# 10125624A00.net
KiCad netlist of a schematic drawn in EAGLE
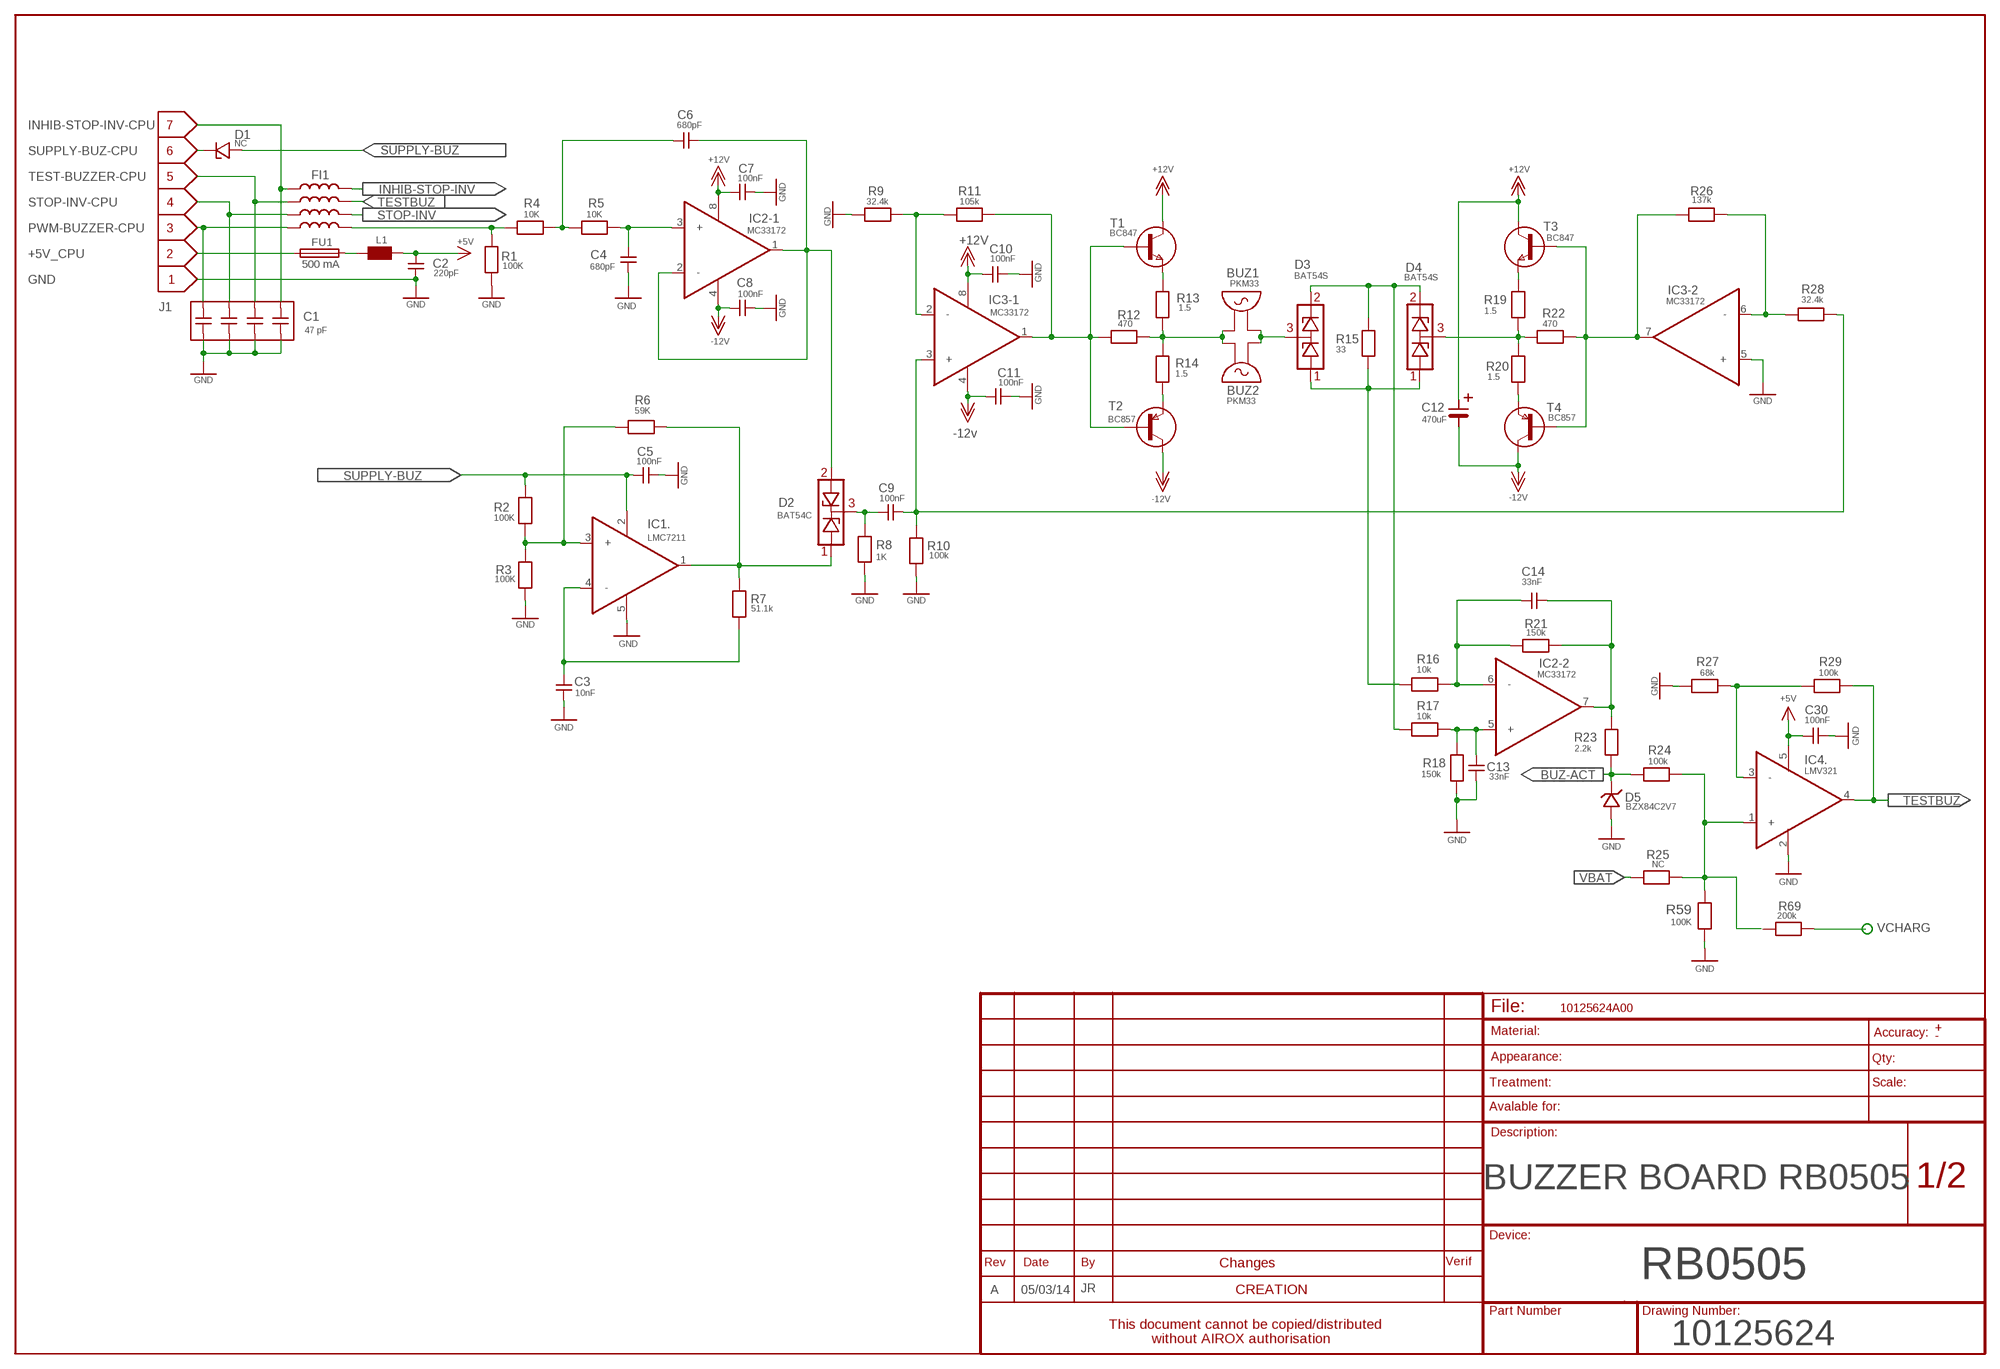
[diagram p0: schematic, sheet 1]
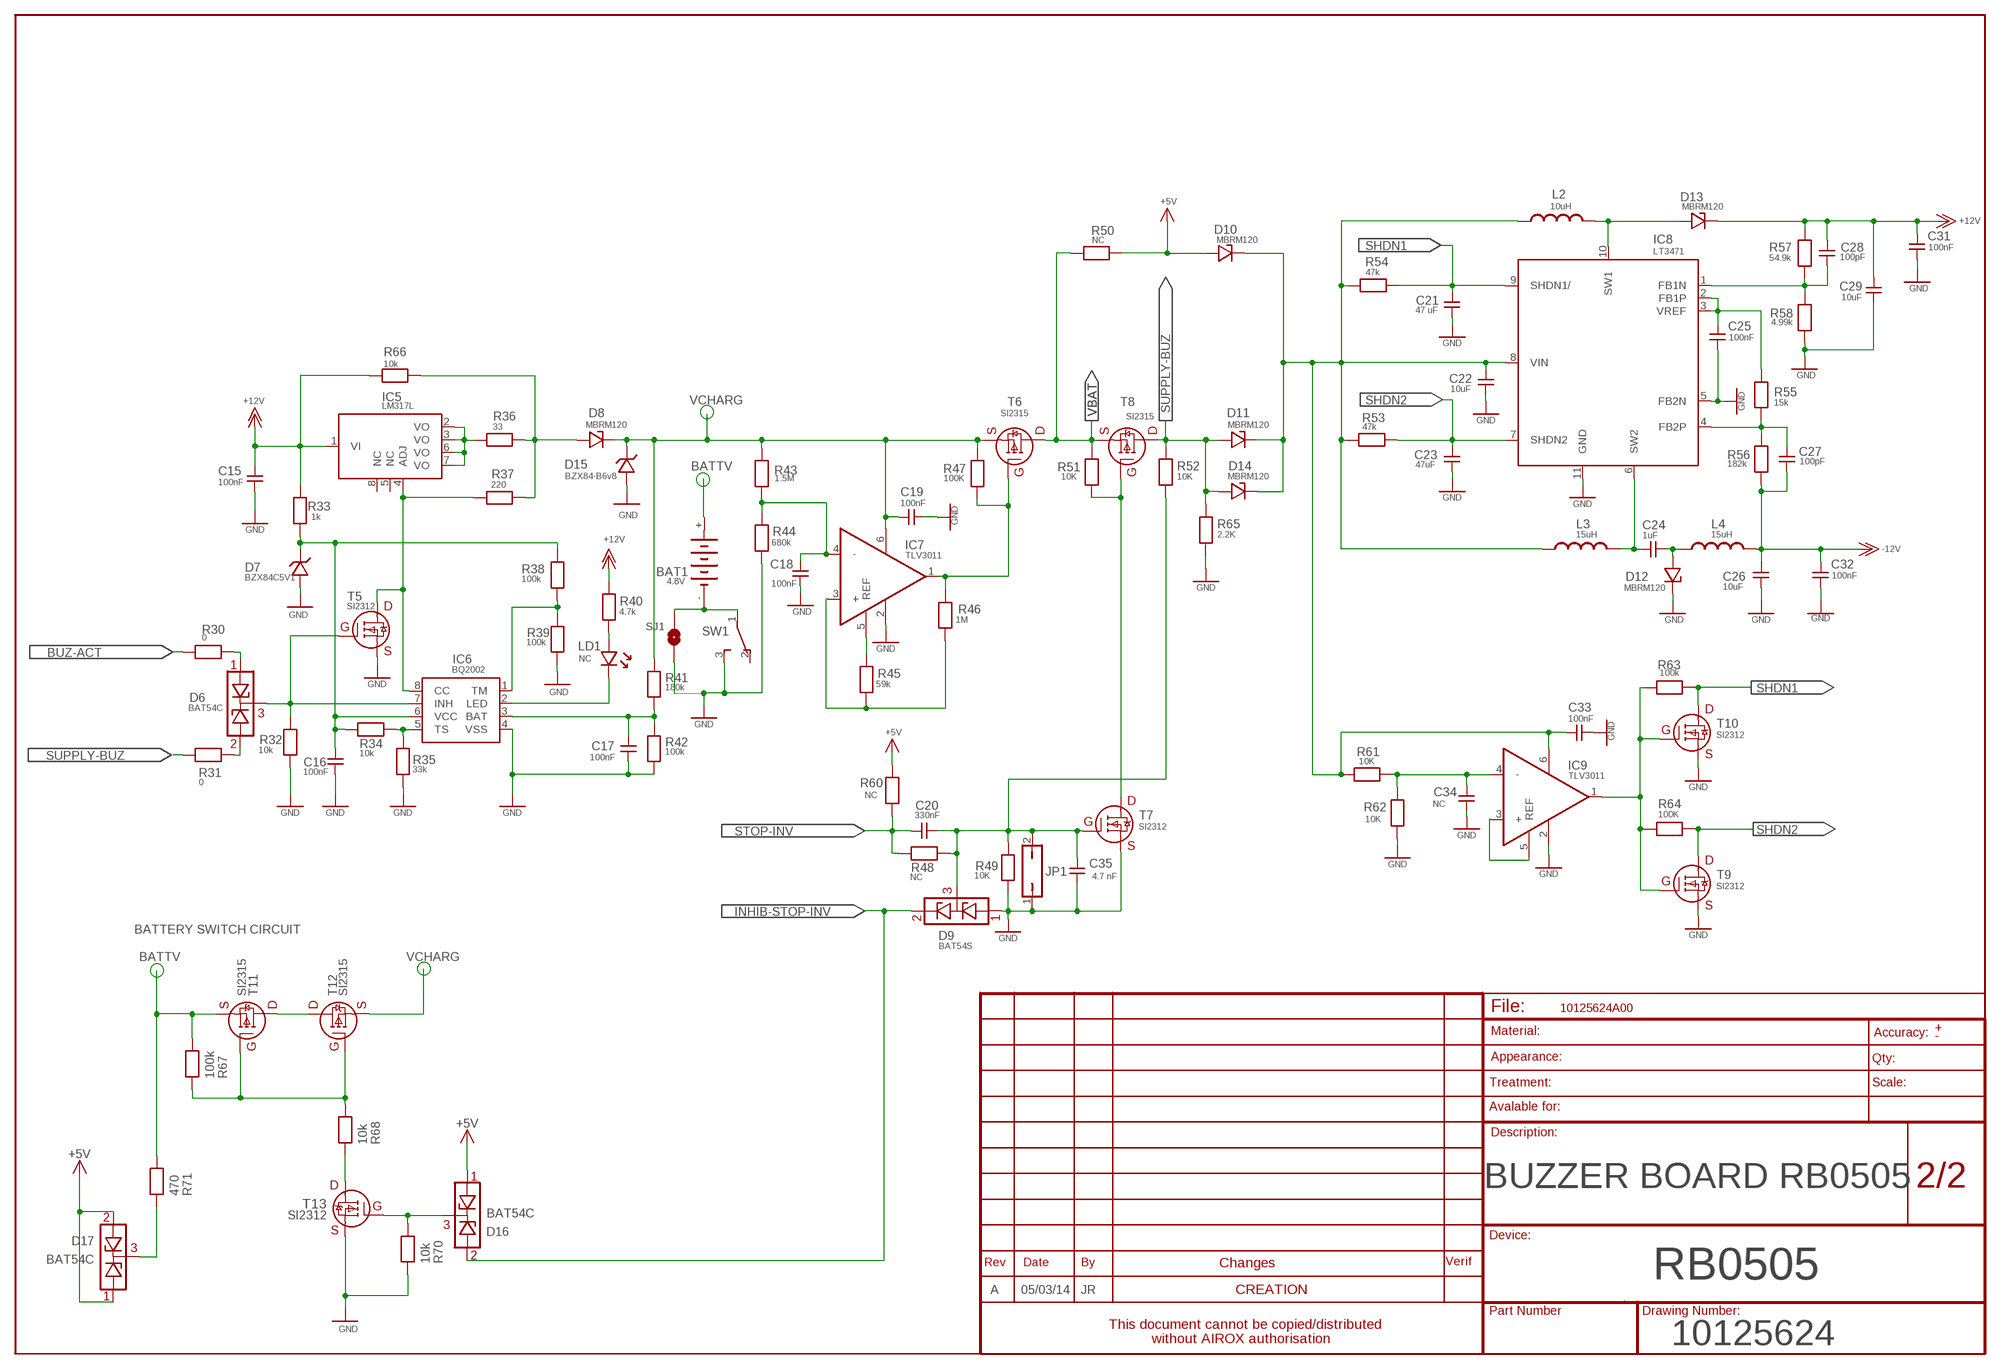
[diagram p1: schematic, sheet 2]

(export (version "E")
  (design (tool "Eeschema 10.0.6"))
  (components
    (comp (ref "BUZ1")
      (value "PKM33")
      (footprint "eagle-import:PKM33")
      (libsource (lib "eagle-import") (part "PKM33"))
    )
    (comp (ref "BUZ2")
      (value "PKM33")
      (footprint "eagle-import:PKM33")
      (libsource (lib "eagle-import") (part "PKM33"))
    )
    (comp (ref "C1")
      (value "47 pF")
      (footprint "eagle-import:RESEAU_1")
      (libsource (lib "eagle-import") (part "RESEAU_4C"))
    )
    (comp (ref "C2")
      (value "220pF")
      (footprint "eagle-import:C0805")
      (libsource (lib "eagle-import") (part "C0805"))
    )
    (comp (ref "C3")
      (value "10nF")
      (footprint "eagle-import:C0805")
      (libsource (lib "eagle-import") (part "C0805"))
    )
    (comp (ref "C4")
      (value "680pF")
      (footprint "eagle-import:C0603")
      (libsource (lib "eagle-import") (part "C0603"))
    )
    (comp (ref "C5")
      (value "100nF")
      (footprint "eagle-import:C0805")
      (libsource (lib "eagle-import") (part "C0805"))
    )
    (comp (ref "C6")
      (value "680pF")
      (footprint "eagle-import:C0603")
      (libsource (lib "eagle-import") (part "C0603"))
    )
    (comp (ref "C7")
      (value "100nF")
      (footprint "eagle-import:C0603")
      (libsource (lib "eagle-import") (part "C0603"))
    )
    (comp (ref "C8")
      (value "100nF")
      (footprint "eagle-import:C0603")
      (libsource (lib "eagle-import") (part "C0603"))
    )
    (comp (ref "C9")
      (value "100nF")
      (footprint "eagle-import:C0805")
      (libsource (lib "eagle-import") (part "CONDENSAT_CMS_C0805"))
    )
    (comp (ref "C10")
      (value "100nF")
      (footprint "eagle-import:C0603")
      (libsource (lib "eagle-import") (part "C0603"))
    )
    (comp (ref "C11")
      (value "100nF")
      (footprint "eagle-import:C0603")
      (libsource (lib "eagle-import") (part "C0603"))
    )
    (comp (ref "C12")
      (value "470uF")
      (footprint "eagle-import:MV100_F")
      (libsource (lib "eagle-import") (part "MV100?F50V"))
    )
    (comp (ref "C13")
      (value "33nF")
      (footprint "eagle-import:C0805")
      (libsource (lib "eagle-import") (part "CONDENSAT_CMS_C0805"))
    )
    (comp (ref "C14")
      (value "33nF")
      (footprint "eagle-import:C0805")
      (libsource (lib "eagle-import") (part "CONDENSAT_CMS_C0805"))
    )
    (comp (ref "C30")
      (value "100nF")
      (footprint "eagle-import:C0805")
      (libsource (lib "eagle-import") (part "CONDENSAT_CMS_C0805"))
    )
    (comp (ref "D1")
      (value "NC")
      (footprint "eagle-import:SOD87")
      (libsource (lib "eagle-import") (part "PRLL5819"))
    )
    (comp (ref "D2")
      (value "BAT54C")
      (footprint "eagle-import:SOT23_DI")
      (libsource (lib "eagle-import") (part "BAT54C"))
    )
    (comp (ref "D3")
      (value "BAT54S")
      (footprint "eagle-import:SOT23DIO")
      (libsource (lib "eagle-import") (part "BAT54S"))
    )
    (comp (ref "D4")
      (value "BAT54S")
      (footprint "eagle-import:SOT23DIO")
      (libsource (lib "eagle-import") (part "BAT54S"))
    )
    (comp (ref "D5")
      (value "BZX84C2V7")
      (footprint "eagle-import:SOT23DIO")
      (libsource (lib "eagle-import") (part "BZX84CXX"))
    )
    (comp (ref "FI1")
      (value "WE-FA")
      (footprint "eagle-import:WE-FA")
      (libsource (lib "eagle-import") (part "WE-FA"))
    )
    (comp (ref "FU1")
      (value "500 mA")
      (footprint "eagle-import:SLOBLO")
      (libsource (lib "eagle-import") (part "SLOBLO"))
    )
    (comp (ref "IC1")
      (value "LMC7211")
      (footprint "eagle-import:SOT23-5")
      (libsource (lib "eagle-import") (part "LMC7211"))
    )
    (comp (ref "IC2")
      (value "MC33172")
      (footprint "eagle-import:SO8")
      (libsource (lib "eagle-import") (part "OPA2604"))
    )
    (comp (ref "IC3")
      (value "MC33172")
      (footprint "eagle-import:SO8")
      (libsource (lib "eagle-import") (part "OPA2604"))
    )
    (comp (ref "IC4")
      (value "LMV321")
      (footprint "eagle-import:SOT23-5")
      (libsource (lib "eagle-import") (part "LMV321"))
    )
    (comp (ref "J1")
      (value "B7B_ZR_SM3_TF")
      (footprint "eagle-import:7B_ZR_SM3_TF")
      (libsource (lib "eagle-import") (part "B7B_ZR_SM3_TF"))
    )
    (comp (ref "L1")
      (value "742792")
      (footprint "eagle-import:0805")
      (libsource (lib "eagle-import") (part "742792"))
    )
    (comp (ref "R1")
      (value "100K")
      (footprint "eagle-import:R0805")
      (libsource (lib "eagle-import") (part "RESIST_CMS_R0805"))
    )
    (comp (ref "R2")
      (value "100K")
      (footprint "eagle-import:R0805")
      (libsource (lib "eagle-import") (part "R0805"))
    )
    (comp (ref "R3")
      (value "100K")
      (footprint "eagle-import:R0805")
      (libsource (lib "eagle-import") (part "R0805"))
    )
    (comp (ref "R4")
      (value "10K")
      (footprint "eagle-import:R0805")
      (libsource (lib "eagle-import") (part "RESIST_CMS_R0805"))
    )
    (comp (ref "R5")
      (value "10K")
      (footprint "eagle-import:R0805")
      (libsource (lib "eagle-import") (part "RESIST_CMS_R0805"))
    )
    (comp (ref "R6")
      (value "59K")
      (footprint "eagle-import:R0805")
      (libsource (lib "eagle-import") (part "R0805"))
    )
    (comp (ref "R7")
      (value "51.1k")
      (footprint "eagle-import:R0805")
      (libsource (lib "eagle-import") (part "R0805"))
    )
    (comp (ref "R8")
      (value "1K")
      (footprint "eagle-import:R0805")
      (libsource (lib "eagle-import") (part "R0805"))
    )
    (comp (ref "R9")
      (value "32.4k")
      (footprint "eagle-import:R0805")
      (libsource (lib "eagle-import") (part "RESIST_CMS_R0805"))
    )
    (comp (ref "R10")
      (value "100k")
      (footprint "eagle-import:R0805")
      (libsource (lib "eagle-import") (part "RESIST_CMS_R0805"))
    )
    (comp (ref "R11")
      (value "105k")
      (footprint "eagle-import:R0805")
      (libsource (lib "eagle-import") (part "RESIST_CMS_R0805"))
    )
    (comp (ref "R12")
      (value "470")
      (footprint "eagle-import:R0805")
      (libsource (lib "eagle-import") (part "RESIST_CMS_R0805"))
    )
    (comp (ref "R13")
      (value "1.5")
      (footprint "eagle-import:R0805")
      (libsource (lib "eagle-import") (part "RESIST_CMS_R0805"))
    )
    (comp (ref "R14")
      (value "1.5")
      (footprint "eagle-import:R0805")
      (libsource (lib "eagle-import") (part "RESIST_CMS_R0805"))
    )
    (comp (ref "R15")
      (value "33")
      (footprint "eagle-import:R0805")
      (libsource (lib "eagle-import") (part "RESIST_CMS_R0805"))
    )
    (comp (ref "R16")
      (value "10k")
      (footprint "eagle-import:R0805")
      (libsource (lib "eagle-import") (part "RESIST_CMS_R0805"))
    )
    (comp (ref "R17")
      (value "10k")
      (footprint "eagle-import:R0805")
      (libsource (lib "eagle-import") (part "RESIST_CMS_R0805"))
    )
    (comp (ref "R18")
      (value "150k")
      (footprint "eagle-import:R0805")
      (libsource (lib "eagle-import") (part "RESIST_CMS_R0805"))
    )
    (comp (ref "R19")
      (value "1.5")
      (footprint "eagle-import:R0805")
      (libsource (lib "eagle-import") (part "RESIST_CMS_R0805"))
    )
    (comp (ref "R20")
      (value "1.5")
      (footprint "eagle-import:R0805")
      (libsource (lib "eagle-import") (part "RESIST_CMS_R0805"))
    )
    (comp (ref "R21")
      (value "150k")
      (footprint "eagle-import:R0805")
      (libsource (lib "eagle-import") (part "RESIST_CMS_R0805"))
    )
    (comp (ref "R22")
      (value "470")
      (footprint "eagle-import:R0805")
      (libsource (lib "eagle-import") (part "RESIST_CMS_R0805"))
    )
    (comp (ref "R23")
      (value "2.2k")
      (footprint "eagle-import:R0805")
      (libsource (lib "eagle-import") (part "RESIST_CMS_R0805"))
    )
    (comp (ref "R24")
      (value "100k")
      (footprint "eagle-import:R0805")
      (libsource (lib "eagle-import") (part "RESIST_CMS_R0805"))
    )
    (comp (ref "R25")
      (value "NC")
      (footprint "eagle-import:R0805")
      (libsource (lib "eagle-import") (part "RESIST_CMS_R0805"))
    )
    (comp (ref "R26")
      (value "137k")
      (footprint "eagle-import:R0805")
      (libsource (lib "eagle-import") (part "RESIST_CMS_R0805"))
    )
    (comp (ref "R27")
      (value "68k")
      (footprint "eagle-import:R0805")
      (libsource (lib "eagle-import") (part "RESIST_CMS_R0805"))
    )
    (comp (ref "R28")
      (value "32.4k")
      (footprint "eagle-import:R0805")
      (libsource (lib "eagle-import") (part "RESIST_CMS_R0805"))
    )
    (comp (ref "R29")
      (value "100k")
      (footprint "eagle-import:R0805")
      (libsource (lib "eagle-import") (part "RESIST_CMS_R0805"))
    )
    (comp (ref "R59")
      (value "100K")
      (footprint "eagle-import:R0805")
      (libsource (lib "eagle-import") (part "RESIST_CMS_R0805"))
    )
    (comp (ref "R69")
      (value "200k")
      (footprint "eagle-import:R0805")
      (libsource (lib "eagle-import") (part "RESIST_CMS_R0805"))
    )
    (comp (ref "T1")
      (value "BC847")
      (footprint "eagle-import:SOT23")
      (libsource (lib "eagle-import") (part "BC847"))
    )
    (comp (ref "T2")
      (value "BC857")
      (footprint "eagle-import:SOT23")
      (libsource (lib "eagle-import") (part "BC547"))
    )
    (comp (ref "T3")
      (value "BC847")
      (footprint "eagle-import:SOT23")
      (libsource (lib "eagle-import") (part "BC847"))
    )
    (comp (ref "T4")
      (value "BC857")
      (footprint "eagle-import:SOT23")
      (libsource (lib "eagle-import") (part "BC547"))
    )
    (comp (ref "BAT1")
      (value "4.8V")
      (footprint "eagle-import:4V110R")
      (libsource (lib "eagle-import") (part "4V110R"))
    )
    (comp (ref "C15")
      (value "100nF")
      (footprint "eagle-import:C0805")
      (libsource (lib "eagle-import") (part "CONDENSA@4_C0805"))
    )
    (comp (ref "C16")
      (value "100nF")
      (footprint "eagle-import:C0805")
      (libsource (lib "eagle-import") (part "CONDENSAT_CMS_C0805"))
    )
    (comp (ref "C17")
      (value "100nF")
      (footprint "eagle-import:C0805")
      (libsource (lib "eagle-import") (part "CONDENSA@4_C0805"))
    )
    (comp (ref "C18")
      (value "100nF")
      (footprint "eagle-import:C0805")
      (libsource (lib "eagle-import") (part "CONDENSA@4_C0805"))
    )
    (comp (ref "C19")
      (value "100nF")
      (footprint "eagle-import:C0805")
      (libsource (lib "eagle-import") (part "CONDENSA@4_C0805"))
    )
    (comp (ref "C20")
      (value "330nF")
      (footprint "eagle-import:C0805")
      (libsource (lib "eagle-import") (part "CONDENSA@4_C0805"))
    )
    (comp (ref "C21")
      (value "47 uF")
      (footprint "eagle-import:C0805")
      (libsource (lib "eagle-import") (part "CONDENSAT_CMS_C0805"))
    )
    (comp (ref "C22")
      (value "10uF")
      (footprint "eagle-import:C0805")
      (libsource (lib "eagle-import") (part "CONDENSAT_CMS_C0805"))
    )
    (comp (ref "C23")
      (value "47uF")
      (footprint "eagle-import:C0805")
      (libsource (lib "eagle-import") (part "CONDENSAT_CMS_C0805"))
    )
    (comp (ref "C24")
      (value "1uF")
      (footprint "eagle-import:C0805")
      (libsource (lib "eagle-import") (part "CONDENSAT_CMS_C0805"))
    )
    (comp (ref "C25")
      (value "100nF")
      (footprint "eagle-import:C0805")
      (libsource (lib "eagle-import") (part "CONDENSAT_CMS_C0805"))
    )
    (comp (ref "C26")
      (value "10uF")
      (footprint "eagle-import:C0805")
      (libsource (lib "eagle-import") (part "CONDENSAT_CMS_C0805"))
    )
    (comp (ref "C27")
      (value "100pF")
      (footprint "eagle-import:C0805")
      (libsource (lib "eagle-import") (part "CONDENSAT_CMS_C0805"))
    )
    (comp (ref "C28")
      (value "100pF")
      (footprint "eagle-import:C0805")
      (libsource (lib "eagle-import") (part "CONDENSAT_CMS_C0805"))
    )
    (comp (ref "C29")
      (value "10uF")
      (footprint "eagle-import:C0805")
      (libsource (lib "eagle-import") (part "CONDENSAT_CMS_C0805"))
    )
    (comp (ref "C31")
      (value "100nF")
      (footprint "eagle-import:C0805")
      (libsource (lib "eagle-import") (part "CONDENSAT_CMS_C0805"))
    )
    (comp (ref "C32")
      (value "100nF")
      (footprint "eagle-import:C0805")
      (libsource (lib "eagle-import") (part "CONDENSAT_CMS_C0805"))
    )
    (comp (ref "C33")
      (value "100nF")
      (footprint "eagle-import:C0805")
      (libsource (lib "eagle-import") (part "CONDENSA@4_C0805"))
    )
    (comp (ref "C34")
      (value "NC")
      (footprint "eagle-import:C0805")
      (libsource (lib "eagle-import") (part "CONDENSA@4_C0805"))
    )
    (comp (ref "C35")
      (value "4.7 nF")
      (footprint "eagle-import:C0805")
      (libsource (lib "eagle-import") (part "CONDENSA@4_C0805"))
    )
    (comp (ref "D6")
      (value "BAT54C")
      (footprint "eagle-import:SOT23_DI")
      (libsource (lib "eagle-import") (part "BAT54C"))
    )
    (comp (ref "D7")
      (value "BZX84C5V1")
      (footprint "eagle-import:SOT23DIO")
      (libsource (lib "eagle-import") (part "BZX84CXX"))
    )
    (comp (ref "D8")
      (value "MBRM120")
      (footprint "eagle-import:SOD87")
      (libsource (lib "eagle-import") (part "PRLL5819"))
    )
    (comp (ref "D9")
      (value "BAT54S")
      (footprint "eagle-import:SOT23DIO")
      (libsource (lib "eagle-import") (part "BAT54S"))
    )
    (comp (ref "D10")
      (value "MBRM120")
      (footprint "eagle-import:SOD87")
      (libsource (lib "eagle-import") (part "PRLL5819"))
    )
    (comp (ref "D11")
      (value "MBRM120")
      (footprint "eagle-import:SOD87")
      (libsource (lib "eagle-import") (part "PRLL5819"))
    )
    (comp (ref "D12")
      (value "MBRM120")
      (footprint "eagle-import:SOD87")
      (libsource (lib "eagle-import") (part "PRLL5819"))
    )
    (comp (ref "D13")
      (value "MBRM120")
      (footprint "eagle-import:SOD87")
      (libsource (lib "eagle-import") (part "PRLL5819"))
    )
    (comp (ref "D14")
      (value "MBRM120")
      (footprint "eagle-import:SOD87")
      (libsource (lib "eagle-import") (part "PRLL5819"))
    )
    (comp (ref "D15")
      (value "BZX84-B6v8")
      (footprint "eagle-import:SOT23DIO")
      (libsource (lib "eagle-import") (part "BZX84CXX"))
    )
    (comp (ref "D16")
      (value "BAT54C")
      (footprint "eagle-import:SOT23_DI")
      (libsource (lib "eagle-import") (part "BAT54C"))
    )
    (comp (ref "D17")
      (value "BAT54C")
      (footprint "eagle-import:SOT23_DI")
      (libsource (lib "eagle-import") (part "BAT54C"))
    )
    (comp (ref "IC5")
      (value "LM317L")
      (footprint "eagle-import:SO8")
      (libsource (lib "eagle-import") (part "LM317L"))
    )
    (comp (ref "IC6")
      (value "BQ2002")
      (footprint "eagle-import:SO8")
      (libsource (lib "eagle-import") (part "BQ2002"))
    )
    (comp (ref "IC7")
      (value "TLV3011")
      (footprint "eagle-import:SOT23-6")
      (libsource (lib "eagle-import") (part "TLV3011"))
    )
    (comp (ref "IC8")
      (value "LT3471")
      (footprint "eagle-import:DFN10")
      (libsource (lib "eagle-import") (part "LT3471"))
    )
    (comp (ref "IC9")
      (value "TLV3011")
      (footprint "eagle-import:SOT23-6")
      (libsource (lib "eagle-import") (part "TLV3011"))
    )
    (comp (ref "JP1")
      (value "JP1Q")
      (footprint "eagle-import:JP1")
      (libsource (lib "eagle-import") (part "JP1Q"))
    )
    (comp (ref "L2")
      (value "10uH")
      (footprint "eagle-import:WE-TPC-MH")
      (libsource (lib "eagle-import") (part "WE-TPC-MH"))
    )
    (comp (ref "L3")
      (value "15uH")
      (footprint "eagle-import:WE-TPC-MH")
      (libsource (lib "eagle-import") (part "WE-TPC-MH"))
    )
    (comp (ref "L4")
      (value "15uH")
      (footprint "eagle-import:WE-TPC-MH")
      (libsource (lib "eagle-import") (part "WE-TPC-MH"))
    )
    (comp (ref "LD1")
      (value "NC")
      (footprint "eagle-import:LED3")
      (libsource (lib "eagle-import") (part "LED3"))
    )
    (comp (ref "R30")
      (value "0")
      (footprint "eagle-import:R0805")
      (libsource (lib "eagle-import") (part "R0805"))
    )
    (comp (ref "R31")
      (value "0")
      (footprint "eagle-import:R0805")
      (libsource (lib "eagle-import") (part "R0805"))
    )
    (comp (ref "R32")
      (value "10k")
      (footprint "eagle-import:R0805")
      (libsource (lib "eagle-import") (part "R0805"))
    )
    (comp (ref "R33")
      (value "1k")
      (footprint "eagle-import:R0805")
      (libsource (lib "eagle-import") (part "R0805"))
    )
    (comp (ref "R34")
      (value "10k")
      (footprint "eagle-import:R0805")
      (libsource (lib "eagle-import") (part "R0805"))
    )
    (comp (ref "R35")
      (value "33k")
      (footprint "eagle-import:R0805")
      (libsource (lib "eagle-import") (part "R0805"))
    )
    (comp (ref "R36")
      (value "33")
      (footprint "eagle-import:R0805")
      (libsource (lib "eagle-import") (part "R0805"))
    )
    (comp (ref "R37")
      (value "220")
      (footprint "eagle-import:R0805")
      (libsource (lib "eagle-import") (part "R0805"))
    )
    (comp (ref "R38")
      (value "100k")
      (footprint "eagle-import:R0805")
      (libsource (lib "eagle-import") (part "R0805"))
    )
    (comp (ref "R39")
      (value "100k")
      (footprint "eagle-import:R0805")
      (libsource (lib "eagle-import") (part "R0805"))
    )
    (comp (ref "R40")
      (value "4.7k")
      (footprint "eagle-import:R0805")
      (libsource (lib "eagle-import") (part "R0805"))
    )
    (comp (ref "R41")
      (value "180k")
      (footprint "eagle-import:R0805")
      (libsource (lib "eagle-import") (part "R0805"))
    )
    (comp (ref "R42")
      (value "100k")
      (footprint "eagle-import:R0805")
      (libsource (lib "eagle-import") (part "R0805"))
    )
    (comp (ref "R43")
      (value "1.5M")
      (footprint "eagle-import:R0805")
      (libsource (lib "eagle-import") (part "R0805"))
    )
    (comp (ref "R44")
      (value "680k")
      (footprint "eagle-import:R0805")
      (libsource (lib "eagle-import") (part "R0805"))
    )
    (comp (ref "R45")
      (value "59k")
      (footprint "eagle-import:R0805")
      (libsource (lib "eagle-import") (part "R0805"))
    )
    (comp (ref "R46")
      (value "1M")
      (footprint "eagle-import:R0805")
      (libsource (lib "eagle-import") (part "R0805"))
    )
    (comp (ref "R47")
      (value "100K")
      (footprint "eagle-import:R0805")
      (libsource (lib "eagle-import") (part "R0805"))
    )
    (comp (ref "R48")
      (value "NC")
      (footprint "eagle-import:R0805")
      (libsource (lib "eagle-import") (part "R0805"))
    )
    (comp (ref "R49")
      (value "10K")
      (footprint "eagle-import:R0805")
      (libsource (lib "eagle-import") (part "R0805"))
    )
    (comp (ref "R50")
      (value "NC")
      (footprint "eagle-import:R0805")
      (libsource (lib "eagle-import") (part "R0805"))
    )
    (comp (ref "R51")
      (value "10K")
      (footprint "eagle-import:R0805")
      (libsource (lib "eagle-import") (part "R0805"))
    )
    (comp (ref "R52")
      (value "10K")
      (footprint "eagle-import:R0805")
      (libsource (lib "eagle-import") (part "R0805"))
    )
    (comp (ref "R53")
      (value "47k")
      (footprint "eagle-import:R0805")
      (libsource (lib "eagle-import") (part "RESIST_CMS_R0805"))
    )
    (comp (ref "R54")
      (value "47k")
      (footprint "eagle-import:R0805")
      (libsource (lib "eagle-import") (part "RESIST_CMS_R0805"))
    )
    (comp (ref "R55")
      (value "15k")
      (footprint "eagle-import:R0805")
      (libsource (lib "eagle-import") (part "RESIST_CMS_R0805"))
    )
    (comp (ref "R56")
      (value "182k")
      (footprint "eagle-import:R0805")
      (libsource (lib "eagle-import") (part "RESIST_CMS_R0805"))
    )
    (comp (ref "R57")
      (value "54.9k")
      (footprint "eagle-import:R0805")
      (libsource (lib "eagle-import") (part "RESIST_CMS_R0805"))
    )
    (comp (ref "R58")
      (value "4.99k")
      (footprint "eagle-import:R0805")
      (libsource (lib "eagle-import") (part "RESIST_CMS_R0805"))
    )
    (comp (ref "R60")
      (value "NC")
      (footprint "eagle-import:R0805")
      (libsource (lib "eagle-import") (part "R0805"))
    )
    (comp (ref "R61")
      (value "10K")
      (footprint "eagle-import:R0805")
      (libsource (lib "eagle-import") (part "R0805"))
    )
    (comp (ref "R62")
      (value "10K")
      (footprint "eagle-import:R0805")
      (libsource (lib "eagle-import") (part "R0805"))
    )
    (comp (ref "R63")
      (value "100k")
      (footprint "eagle-import:R0805")
      (libsource (lib "eagle-import") (part "R0805"))
    )
    (comp (ref "R64")
      (value "100K")
      (footprint "eagle-import:R0805")
      (libsource (lib "eagle-import") (part "R0805"))
    )
    (comp (ref "R65")
      (value "2.2K")
      (footprint "eagle-import:R0805")
      (libsource (lib "eagle-import") (part "R0805"))
    )
    (comp (ref "R66")
      (value "10k")
      (footprint "eagle-import:R0805")
      (libsource (lib "eagle-import") (part "R0805"))
    )
    (comp (ref "R67")
      (value "100k")
      (footprint "eagle-import:R0805")
      (libsource (lib "eagle-import") (part "R0805"))
    )
    (comp (ref "R68")
      (value "10k")
      (footprint "eagle-import:R0805")
      (libsource (lib "eagle-import") (part "R0805"))
    )
    (comp (ref "R70")
      (value "10k")
      (footprint "eagle-import:R0805")
      (libsource (lib "eagle-import") (part "R0805"))
    )
    (comp (ref "R71")
      (value "470")
      (footprint "eagle-import:R0805")
      (libsource (lib "eagle-import") (part "R0805"))
    )
    (comp (ref "SJ1")
      (value "SJW")
      (footprint "eagle-import:SJW")
      (libsource (lib "eagle-import") (part "SJW"))
    )
    (comp (ref "SW1")
      (value "NK236")
      (footprint "eagle-import:NK236")
      (libsource (lib "eagle-import") (part "NK236"))
    )
    (comp (ref "T5")
      (value "SI2312")
      (footprint "eagle-import:SOT23MOS")
      (libsource (lib "eagle-import") (part "IRLML2803"))
    )
    (comp (ref "T6")
      (value "SI2315")
      (footprint "eagle-import:SOT23MOS")
      (libsource (lib "eagle-import") (part "IRLML5103"))
    )
    (comp (ref "T7")
      (value "SI2312")
      (footprint "eagle-import:SOT23MOS")
      (libsource (lib "eagle-import") (part "IRLML2803"))
    )
    (comp (ref "T8")
      (value "SI2315")
      (footprint "eagle-import:SOT23MOS")
      (libsource (lib "eagle-import") (part "IRLML5103"))
    )
    (comp (ref "T9")
      (value "SI2312")
      (footprint "eagle-import:SOT23MOS")
      (libsource (lib "eagle-import") (part "IRLML2803"))
    )
    (comp (ref "T10")
      (value "SI2312")
      (footprint "eagle-import:SOT23MOS")
      (libsource (lib "eagle-import") (part "IRLML2803"))
    )
    (comp (ref "T11")
      (value "SI2315")
      (footprint "eagle-import:SOT23MOS")
      (libsource (lib "eagle-import") (part "IRLML5103"))
    )
    (comp (ref "T12")
      (value "SI2315")
      (footprint "eagle-import:SOT23MOS")
      (libsource (lib "eagle-import") (part "IRLML5103"))
    )
    (comp (ref "T13")
      (value "SI2312")
      (footprint "eagle-import:SOT23MOS")
      (libsource (lib "eagle-import") (part "IRLML2803"))
    )
  )
  (nets
    (net (code "1") (name "+5V") (class "Default")
      (node (ref "C2") (pin "2") (pinfunction "2_2") (pintype "passive"))
      (node (ref "C30") (pin "1") (pinfunction "1_1") (pintype "passive"))
      (node (ref "D10") (pin "A") (pinfunction "A_A") (pintype "passive"))
      (node (ref "D16") (pin "1") (pinfunction "1_1") (pintype "passive"))
      (node (ref "D17") (pin "1") (pinfunction "1_1") (pintype "passive"))
      (node (ref "D17") (pin "2") (pinfunction "2_2") (pintype "bidirectional"))
      (node (ref "IC4") (pin "5") (pinfunction "VCC_5") (pintype "bidirectional"))
      (node (ref "L1") (pin "2") (pinfunction "P$2_2") (pintype "bidirectional"))
      (node (ref "R50") (pin "2") (pinfunction "2_2") (pintype "bidirectional"))
      (node (ref "R60") (pin "2") (pinfunction "2_2") (pintype "bidirectional"))
    )
    (net (code "2") (name "+5V_CPU") (class "Default")
      (node (ref "FU1") (pin "1") (pinfunction "1_1") (pintype "bidirectional"))
      (node (ref "J1") (pin "2") (pinfunction "2_2") (pintype "bidirectional"))
    )
    (net (code "3") (name "+12V") (class "Default")
      (node (ref "C10") (pin "2") (pinfunction "2_2") (pintype "passive"))
      (node (ref "C12") (pin "+") (pinfunction "+_+") (pintype "passive"))
      (node (ref "C15") (pin "2") (pinfunction "2_2") (pintype "passive"))
      (node (ref "C28") (pin "2") (pinfunction "2_2") (pintype "passive"))
      (node (ref "C29") (pin "2") (pinfunction "2_2") (pintype "passive"))
      (node (ref "C31") (pin "2") (pinfunction "2_2") (pintype "passive"))
      (node (ref "C7") (pin "1") (pinfunction "1_1") (pintype "passive"))
      (node (ref "D13") (pin "K") (pinfunction "K_K") (pintype "passive"))
      (node (ref "IC2") (pin "8") (pinfunction "VCC_8") (pintype "bidirectional"))
      (node (ref "IC3") (pin "8") (pinfunction "VCC_8") (pintype "bidirectional"))
      (node (ref "IC5") (pin "1") (pinfunction "VI_1") (pintype "bidirectional"))
      (node (ref "R33") (pin "2") (pinfunction "2_2") (pintype "bidirectional"))
      (node (ref "R40") (pin "1") (pinfunction "1_1") (pintype "bidirectional"))
      (node (ref "R57") (pin "1") (pinfunction "1_1") (pintype "bidirectional"))
      (node (ref "R66") (pin "2") (pinfunction "2_2") (pintype "bidirectional"))
      (node (ref "T1") (pin "C") (pinfunction "C_C") (pintype "passive"))
      (node (ref "T3") (pin "C") (pinfunction "C_C") (pintype "passive"))
    )
    (net (code "4") (name "-12V") (class "Default")
      (node (ref "C11") (pin "2") (pinfunction "2_2") (pintype "passive"))
      (node (ref "C12") (pin "-") (pinfunction "-_-") (pintype "passive"))
      (node (ref "C26") (pin "1") (pinfunction "1_1") (pintype "passive"))
      (node (ref "C27") (pin "1") (pinfunction "1_1") (pintype "passive"))
      (node (ref "C32") (pin "2") (pinfunction "2_2") (pintype "passive"))
      (node (ref "C8") (pin "1") (pinfunction "1_1") (pintype "passive"))
      (node (ref "IC2") (pin "4") (pinfunction "GND_4") (pintype "bidirectional"))
      (node (ref "IC3") (pin "4") (pinfunction "GND_4") (pintype "bidirectional"))
      (node (ref "L4") (pin "2") (pinfunction "2_2") (pintype "bidirectional"))
      (node (ref "R56") (pin "2") (pinfunction "2_2") (pintype "bidirectional"))
      (node (ref "T2") (pin "C") (pinfunction "C_C") (pintype "passive"))
      (node (ref "T4") (pin "C") (pinfunction "C_C") (pintype "passive"))
    )
    (net (code "5") (name "BATTV") (class "Default")
      (node (ref "R67") (pin "2") (pinfunction "2_2") (pintype "bidirectional"))
      (node (ref "R71") (pin "2") (pinfunction "2_2") (pintype "bidirectional"))
      (node (ref "T11") (pin "S") (pinfunction "S_S") (pintype "passive"))
    )
    (net (code "6") (name "BUZ-ACT") (class "Default")
      (node (ref "D5") (pin "3") (pinfunction "K_3") (pintype "passive"))
      (node (ref "R23") (pin "2") (pinfunction "2_2") (pintype "bidirectional"))
      (node (ref "R24") (pin "2") (pinfunction "2_2") (pintype "bidirectional"))
      (node (ref "R30") (pin "1") (pinfunction "1_1") (pintype "bidirectional"))
    )
    (net (code "7") (name "GND") (class "Default")
      (node (ref "C1") (pin "1") (pinfunction "1_1") (pintype "passive"))
      (node (ref "C1") (pin "2") (pinfunction "2_2") (pintype "passive"))
      (node (ref "C1") (pin "3") (pinfunction "3_3") (pintype "passive"))
      (node (ref "C1") (pin "4") (pinfunction "4_4") (pintype "passive"))
      (node (ref "C10") (pin "1") (pinfunction "1_1") (pintype "passive"))
      (node (ref "C11") (pin "1") (pinfunction "1_1") (pintype "passive"))
      (node (ref "C13") (pin "2") (pinfunction "2_2") (pintype "passive"))
      (node (ref "C15") (pin "1") (pinfunction "1_1") (pintype "passive"))
      (node (ref "C16") (pin "2") (pinfunction "2_2") (pintype "passive"))
      (node (ref "C17") (pin "1") (pinfunction "1_1") (pintype "passive"))
      (node (ref "C18") (pin "2") (pinfunction "2_2") (pintype "passive"))
      (node (ref "C19") (pin "2") (pinfunction "2_2") (pintype "passive"))
      (node (ref "C2") (pin "1") (pinfunction "1_1") (pintype "passive"))
      (node (ref "C21") (pin "1") (pinfunction "1_1") (pintype "passive"))
      (node (ref "C22") (pin "2") (pinfunction "2_2") (pintype "passive"))
      (node (ref "C23") (pin "1") (pinfunction "1_1") (pintype "passive"))
      (node (ref "C25") (pin "1") (pinfunction "1_1") (pintype "passive"))
      (node (ref "C26") (pin "2") (pinfunction "2_2") (pintype "passive"))
      (node (ref "C29") (pin "1") (pinfunction "1_1") (pintype "passive"))
      (node (ref "C3") (pin "1") (pinfunction "1_1") (pintype "passive"))
      (node (ref "C30") (pin "2") (pinfunction "2_2") (pintype "passive"))
      (node (ref "C31") (pin "1") (pinfunction "1_1") (pintype "passive"))
      (node (ref "C32") (pin "1") (pinfunction "1_1") (pintype "passive"))
      (node (ref "C33") (pin "2") (pinfunction "2_2") (pintype "passive"))
      (node (ref "C34") (pin "1") (pinfunction "1_1") (pintype "passive"))
      (node (ref "C35") (pin "1") (pinfunction "1_1") (pintype "passive"))
      (node (ref "C4") (pin "2") (pinfunction "2_2") (pintype "passive"))
      (node (ref "C5") (pin "2") (pinfunction "2_2") (pintype "passive"))
      (node (ref "C7") (pin "2") (pinfunction "2_2") (pintype "passive"))
      (node (ref "C8") (pin "2") (pinfunction "2_2") (pintype "passive"))
      (node (ref "D12") (pin "K") (pinfunction "K_K") (pintype "passive"))
      (node (ref "D15") (pin "1") (pinfunction "A_1") (pintype "passive"))
      (node (ref "D5") (pin "1") (pinfunction "A_1") (pintype "passive"))
      (node (ref "D7") (pin "1") (pinfunction "A_1") (pintype "passive"))
      (node (ref "D9") (pin "1") (pinfunction "1_1") (pintype "passive"))
      (node (ref "IC1") (pin "5") (pinfunction "GND_5") (pintype "bidirectional"))
      (node (ref "IC3") (pin "5") (pinfunction "+_5") (pintype "input"))
      (node (ref "IC4") (pin "2") (pinfunction "GND_2") (pintype "bidirectional"))
      (node (ref "IC6") (pin "4") (pinfunction "VSS_4") (pintype "bidirectional"))
      (node (ref "IC7") (pin "2") (pinfunction "VSS_2") (pintype "bidirectional"))
      (node (ref "IC8") (pin "11") (pinfunction "GND_11") (pintype "bidirectional"))
      (node (ref "IC8") (pin "5") (pinfunction "FB2N_5") (pintype "bidirectional"))
      (node (ref "IC9") (pin "2") (pinfunction "VSS_2") (pintype "bidirectional"))
      (node (ref "J1") (pin "1") (pinfunction "1_1") (pintype "bidirectional"))
      (node (ref "JP1") (pin "1") (pinfunction "1_1") (pintype "passive"))
      (node (ref "R1") (pin "1") (pinfunction "1_1") (pintype "bidirectional"))
      (node (ref "R10") (pin "1") (pinfunction "1_1") (pintype "bidirectional"))
      (node (ref "R18") (pin "1") (pinfunction "1_1") (pintype "bidirectional"))
      (node (ref "R27") (pin "2") (pinfunction "2_2") (pintype "bidirectional"))
      (node (ref "R3") (pin "1") (pinfunction "1_1") (pintype "bidirectional"))
      (node (ref "R32") (pin "1") (pinfunction "1_1") (pintype "bidirectional"))
      (node (ref "R35") (pin "1") (pinfunction "1_1") (pintype "bidirectional"))
      (node (ref "R39") (pin "1") (pinfunction "1_1") (pintype "bidirectional"))
      (node (ref "R42") (pin "2") (pinfunction "2_2") (pintype "bidirectional"))
      (node (ref "R44") (pin "1") (pinfunction "1_1") (pintype "bidirectional"))
      (node (ref "R49") (pin "1") (pinfunction "1_1") (pintype "bidirectional"))
      (node (ref "R58") (pin "2") (pinfunction "2_2") (pintype "bidirectional"))
      (node (ref "R59") (pin "1") (pinfunction "1_1") (pintype "bidirectional"))
      (node (ref "R62") (pin "1") (pinfunction "1_1") (pintype "bidirectional"))
      (node (ref "R65") (pin "1") (pinfunction "1_1") (pintype "bidirectional"))
      (node (ref "R70") (pin "1") (pinfunction "1_1") (pintype "bidirectional"))
      (node (ref "R8") (pin "2") (pinfunction "2_2") (pintype "bidirectional"))
      (node (ref "R9") (pin "1") (pinfunction "1_1") (pintype "bidirectional"))
      (node (ref "SJ1") (pin "1") (pinfunction "1_1") (pintype "passive"))
      (node (ref "SW1") (pin "3") (pinfunction "3_3") (pintype "passive"))
      (node (ref "T10") (pin "S") (pinfunction "S_S") (pintype "passive"))
      (node (ref "T13") (pin "S") (pinfunction "S_S") (pintype "passive"))
      (node (ref "T5") (pin "S") (pinfunction "S_S") (pintype "passive"))
      (node (ref "T7") (pin "S") (pinfunction "S_S") (pintype "passive"))
      (node (ref "T9") (pin "S") (pinfunction "S_S") (pintype "passive"))
    )
    (net (code "8") (name "INHIB-STOP-INV") (class "Default")
      (node (ref "D16") (pin "2") (pinfunction "2_2") (pintype "bidirectional"))
      (node (ref "D9") (pin "2") (pinfunction "2_2") (pintype "bidirectional"))
      (node (ref "FI1") (pin "L4A") (pinfunction "L4A_L4A") (pintype "bidirectional"))
    )
    (net (code "9") (name "INHIB-STOP-INV-CPU") (class "Default")
      (node (ref "C1") (pin "8") (pinfunction "8_8") (pintype "passive"))
      (node (ref "FI1") (pin "L4B") (pinfunction "L4B_L4B") (pintype "bidirectional"))
      (node (ref "J1") (pin "7") (pinfunction "7_7") (pintype "bidirectional"))
    )
    (net (code "10") (name "Net-(BAT1-Pad-)") (class "Default")
      (node (ref "BAT1") (pin "-") (pinfunction "-_-") (pintype "passive"))
      (node (ref "SJ1") (pin "2") (pinfunction "2_2") (pintype "passive"))
      (node (ref "SW1") (pin "1") (pinfunction "1_1") (pintype "passive"))
    )
    (net (code "11") (name "Net-(BUZ1-1)") (class "Default")
      (node (ref "BUZ1") (pin "IN+") (pinfunction "1_IN+") (pintype "passive"))
      (node (ref "BUZ2") (pin "IN+") (pinfunction "1_IN+") (pintype "passive"))
      (node (ref "D3") (pin "3") (pinfunction "3_3") (pintype "passive"))
    )
    (net (code "12") (name "Net-(BUZ1-2)") (class "Default")
      (node (ref "BUZ1") (pin "IN-") (pinfunction "2_IN-") (pintype "passive"))
      (node (ref "BUZ2") (pin "IN-") (pinfunction "2_IN-") (pintype "passive"))
      (node (ref "R12") (pin "2") (pinfunction "2_2") (pintype "bidirectional"))
      (node (ref "R13") (pin "1") (pinfunction "1_1") (pintype "bidirectional"))
      (node (ref "R14") (pin "2") (pinfunction "2_2") (pintype "bidirectional"))
    )
    (net (code "13") (name "Net-(C6-Pad2)") (class "Default")
      (node (ref "C6") (pin "2") (pinfunction "2_2") (pintype "passive"))
      (node (ref "R4") (pin "1") (pinfunction "1_1") (pintype "bidirectional"))
      (node (ref "R5") (pin "2") (pinfunction "2_2") (pintype "bidirectional"))
    )
    (net (code "14") (name "Net-(C9-Pad2)") (class "Default")
      (node (ref "C9") (pin "2") (pinfunction "2_2") (pintype "passive"))
      (node (ref "D2") (pin "3") (pinfunction "3_3") (pintype "passive"))
      (node (ref "R8") (pin "1") (pinfunction "1_1") (pintype "bidirectional"))
    )
    (net (code "15") (name "Net-(C20-Pad1)") (class "Default")
      (node (ref "C20") (pin "1") (pinfunction "1_1") (pintype "passive"))
      (node (ref "C35") (pin "2") (pinfunction "2_2") (pintype "passive"))
      (node (ref "D9") (pin "3") (pinfunction "3_3") (pintype "passive"))
      (node (ref "JP1") (pin "2") (pinfunction "2_2") (pintype "passive"))
      (node (ref "R48") (pin "2") (pinfunction "2_2") (pintype "bidirectional"))
      (node (ref "R49") (pin "2") (pinfunction "2_2") (pintype "bidirectional"))
      (node (ref "R52") (pin "1") (pinfunction "1_1") (pintype "bidirectional"))
      (node (ref "T7") (pin "G") (pinfunction "G_G") (pintype "passive"))
    )
    (net (code "16") (name "Net-(C24-Pad1)") (class "Default")
      (node (ref "C24") (pin "1") (pinfunction "1_1") (pintype "passive"))
      (node (ref "D12") (pin "A") (pinfunction "A_A") (pintype "passive"))
      (node (ref "L4") (pin "1") (pinfunction "1_1") (pintype "bidirectional"))
    )
    (net (code "17") (name "Net-(D3-Pad1)") (class "Default")
      (node (ref "D3") (pin "1") (pinfunction "1_1") (pintype "passive"))
      (node (ref "D4") (pin "1") (pinfunction "1_1") (pintype "passive"))
      (node (ref "R15") (pin "1") (pinfunction "1_1") (pintype "bidirectional"))
      (node (ref "R16") (pin "1") (pinfunction "1_1") (pintype "bidirectional"))
    )
    (net (code "18") (name "Net-(D3-Pad2)") (class "Default")
      (node (ref "D3") (pin "2") (pinfunction "2_2") (pintype "bidirectional"))
      (node (ref "D4") (pin "2") (pinfunction "2_2") (pintype "bidirectional"))
      (node (ref "R15") (pin "2") (pinfunction "2_2") (pintype "bidirectional"))
      (node (ref "R17") (pin "1") (pinfunction "1_1") (pintype "bidirectional"))
    )
    (net (code "19") (name "Net-(D4-Pad3)") (class "Default")
      (node (ref "D4") (pin "3") (pinfunction "3_3") (pintype "passive"))
      (node (ref "R19") (pin "1") (pinfunction "1_1") (pintype "bidirectional"))
      (node (ref "R20") (pin "2") (pinfunction "2_2") (pintype "bidirectional"))
      (node (ref "R22") (pin "1") (pinfunction "1_1") (pintype "bidirectional"))
    )
    (net (code "20") (name "Net-(D6-Pad1)") (class "Default")
      (node (ref "D6") (pin "1") (pinfunction "1_1") (pintype "passive"))
      (node (ref "R30") (pin "2") (pinfunction "2_2") (pintype "bidirectional"))
    )
    (net (code "21") (name "Net-(D6-Pad2)") (class "Default")
      (node (ref "D6") (pin "2") (pinfunction "2_2") (pintype "bidirectional"))
      (node (ref "R31") (pin "2") (pinfunction "2_2") (pintype "bidirectional"))
    )
    (net (code "22") (name "Net-(D7-K)") (class "Default")
      (node (ref "C16") (pin "1") (pinfunction "1_1") (pintype "passive"))
      (node (ref "D7") (pin "3") (pinfunction "K_3") (pintype "passive"))
      (node (ref "IC6") (pin "6") (pinfunction "VCC_6") (pintype "bidirectional"))
      (node (ref "R33") (pin "1") (pinfunction "1_1") (pintype "bidirectional"))
      (node (ref "R34") (pin "2") (pinfunction "2_2") (pintype "bidirectional"))
      (node (ref "R38") (pin "2") (pinfunction "2_2") (pintype "bidirectional"))
    )
    (net (code "23") (name "Net-(D8-PadA)") (class "Default")
      (node (ref "D8") (pin "A") (pinfunction "A_A") (pintype "passive"))
      (node (ref "R36") (pin "1") (pinfunction "1_1") (pintype "bidirectional"))
      (node (ref "R37") (pin "1") (pinfunction "1_1") (pintype "bidirectional"))
      (node (ref "R66") (pin "1") (pinfunction "1_1") (pintype "bidirectional"))
    )
    (net (code "24") (name "Net-(D16-Pad3)") (class "Default")
      (node (ref "D16") (pin "3") (pinfunction "3_3") (pintype "passive"))
      (node (ref "R70") (pin "2") (pinfunction "2_2") (pintype "bidirectional"))
      (node (ref "T13") (pin "G") (pinfunction "G_G") (pintype "passive"))
    )
    (net (code "25") (name "Net-(D17-Pad3)") (class "Default")
      (node (ref "D17") (pin "3") (pinfunction "3_3") (pintype "passive"))
      (node (ref "R71") (pin "1") (pinfunction "1_1") (pintype "bidirectional"))
    )
    (net (code "26") (name "Net-(FI1-PadL1A)") (class "Default")
      (node (ref "FI1") (pin "L1A") (pinfunction "L1A_L1A") (pintype "bidirectional"))
      (node (ref "R1") (pin "2") (pinfunction "2_2") (pintype "bidirectional"))
      (node (ref "R4") (pin "2") (pinfunction "2_2") (pintype "bidirectional"))
    )
    (net (code "27") (name "Net-(IC1A-+)") (class "Default")
      (node (ref "IC1") (pin "3") (pinfunction "+_3") (pintype "input"))
      (node (ref "R2") (pin "1") (pinfunction "1_1") (pintype "bidirectional"))
      (node (ref "R3") (pin "2") (pinfunction "2_2") (pintype "bidirectional"))
      (node (ref "R6") (pin "1") (pinfunction "1_1") (pintype "bidirectional"))
    )
    (net (code "28") (name "Net-(IC1A--)") (class "Default")
      (node (ref "C3") (pin "2") (pinfunction "2_2") (pintype "passive"))
      (node (ref "IC1") (pin "4") (pinfunction "-_4") (pintype "input"))
      (node (ref "R7") (pin "1") (pinfunction "1_1") (pintype "bidirectional"))
    )
    (net (code "29") (name "Net-(IC1A-OUT)") (class "Default")
      (node (ref "D2") (pin "1") (pinfunction "1_1") (pintype "passive"))
      (node (ref "IC1") (pin "1") (pinfunction "OUT_1") (pintype "output"))
      (node (ref "R6") (pin "2") (pinfunction "2_2") (pintype "bidirectional"))
      (node (ref "R7") (pin "2") (pinfunction "2_2") (pintype "bidirectional"))
    )
    (net (code "30") (name "Net-(IC2A-+)") (class "Default")
      (node (ref "C4") (pin "1") (pinfunction "1_1") (pintype "passive"))
      (node (ref "IC2") (pin "3") (pinfunction "+_3") (pintype "input"))
      (node (ref "R5") (pin "1") (pinfunction "1_1") (pintype "bidirectional"))
    )
    (net (code "31") (name "Net-(IC2A--)") (class "Default")
      (node (ref "C6") (pin "1") (pinfunction "1_1") (pintype "passive"))
      (node (ref "D2") (pin "2") (pinfunction "2_2") (pintype "bidirectional"))
      (node (ref "IC2") (pin "1") (pinfunction "OUT_1") (pintype "output"))
      (node (ref "IC2") (pin "2") (pinfunction "-_2") (pintype "input"))
    )
    (net (code "32") (name "Net-(IC2B-+)") (class "Default")
      (node (ref "C13") (pin "1") (pinfunction "1_1") (pintype "passive"))
      (node (ref "IC2") (pin "5") (pinfunction "+_5") (pintype "input"))
      (node (ref "R17") (pin "2") (pinfunction "2_2") (pintype "bidirectional"))
      (node (ref "R18") (pin "2") (pinfunction "2_2") (pintype "bidirectional"))
    )
    (net (code "33") (name "Net-(IC2B--)") (class "Default")
      (node (ref "C14") (pin "1") (pinfunction "1_1") (pintype "passive"))
      (node (ref "IC2") (pin "6") (pinfunction "-_6") (pintype "input"))
      (node (ref "R16") (pin "2") (pinfunction "2_2") (pintype "bidirectional"))
      (node (ref "R21") (pin "1") (pinfunction "1_1") (pintype "bidirectional"))
    )
    (net (code "34") (name "Net-(IC2B-OUT)") (class "Default")
      (node (ref "C14") (pin "2") (pinfunction "2_2") (pintype "passive"))
      (node (ref "IC2") (pin "7") (pinfunction "OUT_7") (pintype "output"))
      (node (ref "R21") (pin "2") (pinfunction "2_2") (pintype "bidirectional"))
      (node (ref "R23") (pin "1") (pinfunction "1_1") (pintype "bidirectional"))
    )
    (net (code "35") (name "Net-(IC3A-+)") (class "Default")
      (node (ref "C9") (pin "1") (pinfunction "1_1") (pintype "passive"))
      (node (ref "IC3") (pin "3") (pinfunction "+_3") (pintype "input"))
      (node (ref "R10") (pin "2") (pinfunction "2_2") (pintype "bidirectional"))
      (node (ref "R28") (pin "2") (pinfunction "2_2") (pintype "bidirectional"))
    )
    (net (code "36") (name "Net-(IC3A--)") (class "Default")
      (node (ref "IC3") (pin "2") (pinfunction "-_2") (pintype "input"))
      (node (ref "R11") (pin "1") (pinfunction "1_1") (pintype "bidirectional"))
      (node (ref "R9") (pin "2") (pinfunction "2_2") (pintype "bidirectional"))
    )
    (net (code "37") (name "Net-(IC3A-OUT)") (class "Default")
      (node (ref "IC3") (pin "1") (pinfunction "OUT_1") (pintype "output"))
      (node (ref "R11") (pin "2") (pinfunction "2_2") (pintype "bidirectional"))
      (node (ref "R12") (pin "1") (pinfunction "1_1") (pintype "bidirectional"))
      (node (ref "T1") (pin "B") (pinfunction "B_B") (pintype "passive"))
      (node (ref "T2") (pin "B") (pinfunction "B_B") (pintype "passive"))
    )
    (net (code "38") (name "Net-(IC3B--)") (class "Default")
      (node (ref "IC3") (pin "6") (pinfunction "-_6") (pintype "input"))
      (node (ref "R26") (pin "2") (pinfunction "2_2") (pintype "bidirectional"))
      (node (ref "R28") (pin "1") (pinfunction "1_1") (pintype "bidirectional"))
    )
    (net (code "39") (name "Net-(IC3B-OUT)") (class "Default")
      (node (ref "IC3") (pin "7") (pinfunction "OUT_7") (pintype "output"))
      (node (ref "R22") (pin "2") (pinfunction "2_2") (pintype "bidirectional"))
      (node (ref "R26") (pin "1") (pinfunction "1_1") (pintype "bidirectional"))
      (node (ref "T3") (pin "B") (pinfunction "B_B") (pintype "passive"))
      (node (ref "T4") (pin "B") (pinfunction "B_B") (pintype "passive"))
    )
    (net (code "40") (name "Net-(IC4A-+)") (class "Default")
      (node (ref "IC4") (pin "1") (pinfunction "+_1") (pintype "input"))
      (node (ref "R24") (pin "1") (pinfunction "1_1") (pintype "bidirectional"))
      (node (ref "R25") (pin "1") (pinfunction "1_1") (pintype "bidirectional"))
      (node (ref "R59") (pin "2") (pinfunction "2_2") (pintype "bidirectional"))
    )
    (net (code "41") (name "Net-(IC4A--)") (class "Default")
      (node (ref "IC4") (pin "3") (pinfunction "-_3") (pintype "input"))
      (node (ref "R27") (pin "1") (pinfunction "1_1") (pintype "bidirectional"))
      (node (ref "R29") (pin "2") (pinfunction "2_2") (pintype "bidirectional"))
    )
    (net (code "42") (name "Net-(IC5-ADJ)") (class "Default")
      (node (ref "IC5") (pin "4") (pinfunction "ADJ_4") (pintype "bidirectional"))
      (node (ref "IC6") (pin "8") (pinfunction "CC_8") (pintype "bidirectional"))
      (node (ref "R37") (pin "2") (pinfunction "2_2") (pintype "bidirectional"))
      (node (ref "T5") (pin "D") (pinfunction "D_D") (pintype "passive"))
    )
    (net (code "43") (name "Net-(IC5-VO-Pad2)") (class "Default")
      (node (ref "IC5") (pin "2") (pinfunction "VO_2") (pintype "bidirectional"))
      (node (ref "IC5") (pin "3") (pinfunction "VO_3") (pintype "bidirectional"))
      (node (ref "IC5") (pin "6") (pinfunction "VO_6") (pintype "bidirectional"))
      (node (ref "IC5") (pin "7") (pinfunction "VO_7") (pintype "bidirectional"))
      (node (ref "R36") (pin "2") (pinfunction "2_2") (pintype "bidirectional"))
    )
    (net (code "44") (name "Net-(IC6-BAT)") (class "Default")
      (node (ref "C17") (pin "2") (pinfunction "2_2") (pintype "passive"))
      (node (ref "IC6") (pin "3") (pinfunction "BAT_3") (pintype "bidirectional"))
      (node (ref "R41") (pin "2") (pinfunction "2_2") (pintype "bidirectional"))
      (node (ref "R42") (pin "1") (pinfunction "1_1") (pintype "bidirectional"))
    )
    (net (code "45") (name "Net-(IC6-INH)") (class "Default")
      (node (ref "D6") (pin "3") (pinfunction "3_3") (pintype "passive"))
      (node (ref "IC6") (pin "7") (pinfunction "INH_7") (pintype "bidirectional"))
      (node (ref "R32") (pin "2") (pinfunction "2_2") (pintype "bidirectional"))
      (node (ref "T5") (pin "G") (pinfunction "G_G") (pintype "passive"))
    )
    (net (code "46") (name "Net-(IC6-LED)") (class "Default")
      (node (ref "IC6") (pin "2") (pinfunction "LED_2") (pintype "bidirectional"))
      (node (ref "LD1") (pin "K") (pinfunction "K_K") (pintype "passive"))
    )
    (net (code "47") (name "Net-(IC6-TM)") (class "Default")
      (node (ref "IC6") (pin "1") (pinfunction "TM_1") (pintype "bidirectional"))
      (node (ref "R38") (pin "1") (pinfunction "1_1") (pintype "bidirectional"))
      (node (ref "R39") (pin "2") (pinfunction "2_2") (pintype "bidirectional"))
    )
    (net (code "48") (name "Net-(IC6-TS)") (class "Default")
      (node (ref "IC6") (pin "5") (pinfunction "TS_5") (pintype "bidirectional"))
      (node (ref "R34") (pin "1") (pinfunction "1_1") (pintype "bidirectional"))
      (node (ref "R35") (pin "2") (pinfunction "2_2") (pintype "bidirectional"))
    )
    (net (code "49") (name "Net-(IC7-+)") (class "Default")
      (node (ref "IC7") (pin "3") (pinfunction "+_3") (pintype "input"))
      (node (ref "R45") (pin "1") (pinfunction "1_1") (pintype "bidirectional"))
      (node (ref "R46") (pin "1") (pinfunction "1_1") (pintype "bidirectional"))
    )
    (net (code "50") (name "Net-(IC7--)") (class "Default")
      (node (ref "C18") (pin "1") (pinfunction "1_1") (pintype "passive"))
      (node (ref "IC7") (pin "4") (pinfunction "-_4") (pintype "input"))
      (node (ref "R43") (pin "1") (pinfunction "1_1") (pintype "bidirectional"))
      (node (ref "R44") (pin "2") (pinfunction "2_2") (pintype "bidirectional"))
    )
    (net (code "51") (name "Net-(IC7-OUT)") (class "Default")
      (node (ref "IC7") (pin "1") (pinfunction "OUT_1") (pintype "output"))
      (node (ref "R46") (pin "2") (pinfunction "2_2") (pintype "bidirectional"))
      (node (ref "R47") (pin "1") (pinfunction "1_1") (pintype "bidirectional"))
      (node (ref "T6") (pin "G") (pinfunction "G_G") (pintype "passive"))
    )
    (net (code "52") (name "Net-(IC7-REF)") (class "Default")
      (node (ref "IC7") (pin "5") (pinfunction "REF_5") (pintype "bidirectional"))
      (node (ref "R45") (pin "2") (pinfunction "2_2") (pintype "bidirectional"))
    )
    (net (code "53") (name "Net-(IC8-FB1N)") (class "Default")
      (node (ref "C28") (pin "1") (pinfunction "1_1") (pintype "passive"))
      (node (ref "IC8") (pin "1") (pinfunction "FB1N_1") (pintype "bidirectional"))
      (node (ref "R57") (pin "2") (pinfunction "2_2") (pintype "bidirectional"))
      (node (ref "R58") (pin "1") (pinfunction "1_1") (pintype "bidirectional"))
    )
    (net (code "54") (name "Net-(IC8-FB1P)") (class "Default")
      (node (ref "C25") (pin "2") (pinfunction "2_2") (pintype "passive"))
      (node (ref "IC8") (pin "2") (pinfunction "FB1P_2") (pintype "bidirectional"))
      (node (ref "IC8") (pin "3") (pinfunction "VREF_3") (pintype "bidirectional"))
      (node (ref "R55") (pin "1") (pinfunction "1_1") (pintype "bidirectional"))
    )
    (net (code "55") (name "Net-(IC8-FB2P)") (class "Default")
      (node (ref "C27") (pin "2") (pinfunction "2_2") (pintype "passive"))
      (node (ref "IC8") (pin "4") (pinfunction "FB2P_4") (pintype "bidirectional"))
      (node (ref "R55") (pin "2") (pinfunction "2_2") (pintype "bidirectional"))
      (node (ref "R56") (pin "1") (pinfunction "1_1") (pintype "bidirectional"))
    )
    (net (code "56") (name "Net-(IC8-SW1)") (class "Default")
      (node (ref "D13") (pin "A") (pinfunction "A_A") (pintype "passive"))
      (node (ref "IC8") (pin "10") (pinfunction "SW1_10") (pintype "bidirectional"))
      (node (ref "L2") (pin "2") (pinfunction "2_2") (pintype "bidirectional"))
    )
    (net (code "57") (name "Net-(IC8-SW2)") (class "Default")
      (node (ref "C24") (pin "2") (pinfunction "2_2") (pintype "passive"))
      (node (ref "IC8") (pin "6") (pinfunction "SW2_6") (pintype "bidirectional"))
      (node (ref "L3") (pin "2") (pinfunction "2_2") (pintype "bidirectional"))
    )
    (net (code "58") (name "Net-(IC8-VIN)") (class "Default")
      (node (ref "C22") (pin "1") (pinfunction "1_1") (pintype "passive"))
      (node (ref "C33") (pin "1") (pinfunction "1_1") (pintype "passive"))
      (node (ref "D10") (pin "K") (pinfunction "K_K") (pintype "passive"))
      (node (ref "D11") (pin "K") (pinfunction "K_K") (pintype "passive"))
      (node (ref "D14") (pin "K") (pinfunction "K_K") (pintype "passive"))
      (node (ref "IC8") (pin "8") (pinfunction "VIN_8") (pintype "bidirectional"))
      (node (ref "IC9") (pin "6") (pinfunction "VCC_6") (pintype "bidirectional"))
      (node (ref "L2") (pin "1") (pinfunction "1_1") (pintype "bidirectional"))
      (node (ref "L3") (pin "1") (pinfunction "1_1") (pintype "bidirectional"))
      (node (ref "R53") (pin "1") (pinfunction "1_1") (pintype "bidirectional"))
      (node (ref "R54") (pin "1") (pinfunction "1_1") (pintype "bidirectional"))
      (node (ref "R61") (pin "2") (pinfunction "2_2") (pintype "bidirectional"))
    )
    (net (code "59") (name "Net-(IC9-+)") (class "Default")
      (node (ref "IC9") (pin "3") (pinfunction "+_3") (pintype "input"))
      (node (ref "IC9") (pin "5") (pinfunction "REF_5") (pintype "bidirectional"))
    )
    (net (code "60") (name "Net-(IC9--)") (class "Default")
      (node (ref "C34") (pin "2") (pinfunction "2_2") (pintype "passive"))
      (node (ref "IC9") (pin "4") (pinfunction "-_4") (pintype "input"))
      (node (ref "R61") (pin "1") (pinfunction "1_1") (pintype "bidirectional"))
      (node (ref "R62") (pin "2") (pinfunction "2_2") (pintype "bidirectional"))
    )
    (net (code "61") (name "Net-(IC9-OUT)") (class "Default")
      (node (ref "IC9") (pin "1") (pinfunction "OUT_1") (pintype "output"))
      (node (ref "R63") (pin "1") (pinfunction "1_1") (pintype "bidirectional"))
      (node (ref "R64") (pin "1") (pinfunction "1_1") (pintype "bidirectional"))
      (node (ref "T10") (pin "G") (pinfunction "G_G") (pintype "passive"))
      (node (ref "T9") (pin "G") (pinfunction "G_G") (pintype "passive"))
    )
    (net (code "62") (name "Net-(L1-P$1)") (class "Default")
      (node (ref "FU1") (pin "2") (pinfunction "2_2") (pintype "bidirectional"))
      (node (ref "L1") (pin "1") (pinfunction "P$1_1") (pintype "bidirectional"))
    )
    (net (code "63") (name "Net-(LD1-PadA)") (class "Default")
      (node (ref "LD1") (pin "A") (pinfunction "A_A") (pintype "passive"))
      (node (ref "R40") (pin "2") (pinfunction "2_2") (pintype "bidirectional"))
    )
    (net (code "64") (name "Net-(R13-Pad2)") (class "Default")
      (node (ref "R13") (pin "2") (pinfunction "2_2") (pintype "bidirectional"))
      (node (ref "T1") (pin "E") (pinfunction "E_E") (pintype "passive"))
    )
    (net (code "65") (name "Net-(R14-Pad1)") (class "Default")
      (node (ref "R14") (pin "1") (pinfunction "1_1") (pintype "bidirectional"))
      (node (ref "T2") (pin "E") (pinfunction "E_E") (pintype "passive"))
    )
    (net (code "66") (name "Net-(R19-Pad2)") (class "Default")
      (node (ref "R19") (pin "2") (pinfunction "2_2") (pintype "bidirectional"))
      (node (ref "T3") (pin "E") (pinfunction "E_E") (pintype "passive"))
    )
    (net (code "67") (name "Net-(R20-Pad1)") (class "Default")
      (node (ref "R20") (pin "1") (pinfunction "1_1") (pintype "bidirectional"))
      (node (ref "T4") (pin "E") (pinfunction "E_E") (pintype "passive"))
    )
    (net (code "68") (name "Net-(R51-Pad1)") (class "Default")
      (node (ref "R51") (pin "1") (pinfunction "1_1") (pintype "bidirectional"))
      (node (ref "T7") (pin "D") (pinfunction "D_D") (pintype "passive"))
      (node (ref "T8") (pin "G") (pinfunction "G_G") (pintype "passive"))
    )
    (net (code "69") (name "Net-(R67-Pad1)") (class "Default")
      (node (ref "R67") (pin "1") (pinfunction "1_1") (pintype "bidirectional"))
      (node (ref "R68") (pin "2") (pinfunction "2_2") (pintype "bidirectional"))
      (node (ref "T11") (pin "G") (pinfunction "G_G") (pintype "passive"))
      (node (ref "T12") (pin "G") (pinfunction "G_G") (pintype "passive"))
    )
    (net (code "70") (name "Net-(R68-Pad1)") (class "Default")
      (node (ref "R68") (pin "1") (pinfunction "1_1") (pintype "bidirectional"))
      (node (ref "T13") (pin "D") (pinfunction "D_D") (pintype "passive"))
    )
    (net (code "71") (name "Net-(T11-PadD)") (class "Default")
      (node (ref "T11") (pin "D") (pinfunction "D_D") (pintype "passive"))
      (node (ref "T12") (pin "D") (pinfunction "D_D") (pintype "passive"))
    )
    (net (code "72") (name "PWM-BUZZER-CPU") (class "Default")
      (node (ref "C1") (pin "5") (pinfunction "5_5") (pintype "passive"))
      (node (ref "FI1") (pin "L1B") (pinfunction "L1B_L1B") (pintype "bidirectional"))
      (node (ref "J1") (pin "3") (pinfunction "3_3") (pintype "bidirectional"))
    )
    (net (code "73") (name "SHDN1") (class "Default")
      (node (ref "C21") (pin "2") (pinfunction "2_2") (pintype "passive"))
      (node (ref "IC8") (pin "9") (pinfunction "SHDN1/_9") (pintype "bidirectional"))
      (node (ref "R54") (pin "2") (pinfunction "2_2") (pintype "bidirectional"))
      (node (ref "R63") (pin "2") (pinfunction "2_2") (pintype "bidirectional"))
      (node (ref "T10") (pin "D") (pinfunction "D_D") (pintype "passive"))
    )
    (net (code "74") (name "SHDN2") (class "Default")
      (node (ref "C23") (pin "2") (pinfunction "2_2") (pintype "passive"))
      (node (ref "IC8") (pin "7") (pinfunction "SHDN2_7") (pintype "bidirectional"))
      (node (ref "R53") (pin "2") (pinfunction "2_2") (pintype "bidirectional"))
      (node (ref "R64") (pin "2") (pinfunction "2_2") (pintype "bidirectional"))
      (node (ref "T9") (pin "D") (pinfunction "D_D") (pintype "passive"))
    )
    (net (code "75") (name "STOP-INV") (class "Default")
      (node (ref "C20") (pin "2") (pinfunction "2_2") (pintype "passive"))
      (node (ref "FI1") (pin "L2A") (pinfunction "L2A_L2A") (pintype "bidirectional"))
      (node (ref "R48") (pin "1") (pinfunction "1_1") (pintype "bidirectional"))
      (node (ref "R60") (pin "1") (pinfunction "1_1") (pintype "bidirectional"))
    )
    (net (code "76") (name "STOP-INV-CPU") (class "Default")
      (node (ref "C1") (pin "6") (pinfunction "6_6") (pintype "passive"))
      (node (ref "FI1") (pin "L2B") (pinfunction "L2B_L2B") (pintype "bidirectional"))
      (node (ref "J1") (pin "4") (pinfunction "4_4") (pintype "bidirectional"))
    )
    (net (code "77") (name "SUPPLY-BUZ") (class "Default")
      (node (ref "C5") (pin "1") (pinfunction "1_1") (pintype "passive"))
      (node (ref "D1") (pin "A") (pinfunction "A_A") (pintype "passive"))
      (node (ref "D11") (pin "A") (pinfunction "A_A") (pintype "passive"))
      (node (ref "D14") (pin "A") (pinfunction "A_A") (pintype "passive"))
      (node (ref "IC1") (pin "2") (pinfunction "VCC_2") (pintype "bidirectional"))
      (node (ref "R2") (pin "2") (pinfunction "2_2") (pintype "bidirectional"))
      (node (ref "R31") (pin "1") (pinfunction "1_1") (pintype "bidirectional"))
      (node (ref "R52") (pin "2") (pinfunction "2_2") (pintype "bidirectional"))
      (node (ref "R65") (pin "2") (pinfunction "2_2") (pintype "bidirectional"))
      (node (ref "T8") (pin "D") (pinfunction "D_D") (pintype "passive"))
    )
    (net (code "78") (name "SUPPLY-BUZ-CPU") (class "Default")
      (node (ref "D1") (pin "K") (pinfunction "K_K") (pintype "passive"))
      (node (ref "J1") (pin "6") (pinfunction "6_6") (pintype "bidirectional"))
    )
    (net (code "79") (name "TEST-BUZZER-CPU") (class "Default")
      (node (ref "C1") (pin "7") (pinfunction "7_7") (pintype "passive"))
      (node (ref "FI1") (pin "L3B") (pinfunction "L3B_L3B") (pintype "bidirectional"))
      (node (ref "J1") (pin "5") (pinfunction "5_5") (pintype "bidirectional"))
    )
    (net (code "80") (name "TESTBUZ") (class "Default")
      (node (ref "FI1") (pin "L3A") (pinfunction "L3A_L3A") (pintype "bidirectional"))
      (node (ref "IC4") (pin "4") (pinfunction "OUT_4") (pintype "output"))
      (node (ref "R29") (pin "1") (pinfunction "1_1") (pintype "bidirectional"))
    )
    (net (code "81") (name "VBAT") (class "Default")
      (node (ref "R25") (pin "2") (pinfunction "2_2") (pintype "bidirectional"))
      (node (ref "R50") (pin "1") (pinfunction "1_1") (pintype "bidirectional"))
      (node (ref "R51") (pin "2") (pinfunction "2_2") (pintype "bidirectional"))
      (node (ref "T6") (pin "D") (pinfunction "D_D") (pintype "passive"))
      (node (ref "T8") (pin "S") (pinfunction "S_S") (pintype "passive"))
    )
    (net (code "82") (name "VCHARG") (class "Default")
      (node (ref "C19") (pin "1") (pinfunction "1_1") (pintype "passive"))
      (node (ref "D15") (pin "3") (pinfunction "K_3") (pintype "passive"))
      (node (ref "D8") (pin "K") (pinfunction "K_K") (pintype "passive"))
      (node (ref "IC7") (pin "6") (pinfunction "VCC_6") (pintype "bidirectional"))
      (node (ref "R41") (pin "1") (pinfunction "1_1") (pintype "bidirectional"))
      (node (ref "R43") (pin "2") (pinfunction "2_2") (pintype "bidirectional"))
      (node (ref "R47") (pin "2") (pinfunction "2_2") (pintype "bidirectional"))
      (node (ref "R69") (pin "1") (pinfunction "1_1") (pintype "bidirectional"))
      (node (ref "T12") (pin "S") (pinfunction "S_S") (pintype "passive"))
      (node (ref "T6") (pin "S") (pinfunction "S_S") (pintype "passive"))
    )
    (net (code "83") (name "unconnected-(BAT1-+-Pad+@1)") (class "Default")
      (node (ref "BAT1") (pin "+@1") (pinfunction "+_+@1") (pintype "passive"))
    )
    (net (code "84") (name "unconnected-(BAT1-Pad+)") (class "Default")
      (node (ref "BAT1") (pin "+") (pinfunction "+_+") (pintype "passive"))
    )
    (net (code "85") (name "unconnected-(IC5-NC-Pad5)") (class "Default")
      (node (ref "IC5") (pin "5") (pinfunction "NC_5") (pintype "bidirectional"))
    )
    (net (code "86") (name "unconnected-(IC5-NC-Pad8)") (class "Default")
      (node (ref "IC5") (pin "8") (pinfunction "NC_8") (pintype "bidirectional"))
    )
    (net (code "87") (name "unconnected-(R69-Pad2)") (class "Default")
      (node (ref "R69") (pin "2") (pinfunction "2_2") (pintype "bidirectional"))
    )
    (net (code "88") (name "unconnected-(SW1-Pad2)") (class "Default")
      (node (ref "SW1") (pin "2") (pinfunction "2_2") (pintype "passive"))
    )
  )
)
